# CoreProcessor.net
KiCad netlist of a schematic drawn in Altium Designer
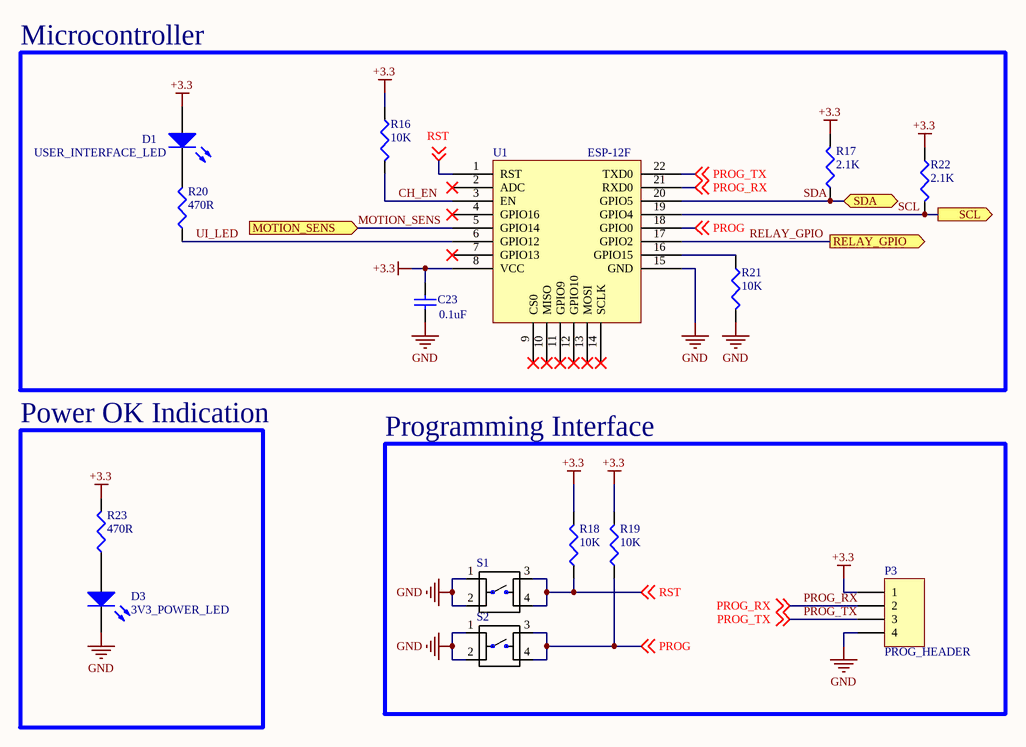
[diagram p0: CoreProcessor.SchDoc]

(export (version "E")
  (design (tool "Eeschema 10.0.6"))
  (components
    (comp (ref "C23")
      (value "0.1uF")
      (footprint "C0603")
      (description "Capacitor (Semiconductor SIM Model)")
      (fields (field (name "Comment") "MUDAR FOOTPRINT") (field (name "PUBLISHER") "Altium Limited"))
      (libsource (lib "Miscellaneous Devices") (part "Cap Semi"))
    )
    (comp (ref "D1")
      (value "USER_INTERFACE_LED")
      (footprint "LED0603")
      (description "Typical INFRARED GaAs LED")
      (fields (field (name "PUBLISHER") "Altium Limited"))
      (libsource (lib "Miscellaneous Devices") (part "LED0"))
    )
    (comp (ref "D3")
      (value "3V3_POWER_LED")
      (footprint "LED0603")
      (description "Typical INFRARED GaAs LED")
      (fields (field (name "PUBLISHER") "Altium Limited"))
      (libsource (lib "Miscellaneous Devices") (part "LED0"))
    )
    (comp (ref "P3")
      (value "PROG_HEADER")
      (footprint "HDR1X4")
      (description "Header, 4-Pin")
      (fields (field (name "PUBLISHER") "Altium Limited"))
      (libsource (lib "Miscellaneous Connectors") (part "Header 4"))
    )
    (comp (ref "R16")
      (value "10K")
      (footprint "R0603")
      (description "Resistor")
      (fields (field (name "Comment") "Res3") (field (name "PUBLISHER") "Altium Limited"))
      (libsource (lib "Miscellaneous Devices") (part "Res3"))
    )
    (comp (ref "R17")
      (value "2.1K")
      (footprint "R0603")
      (description "Resistor")
      (fields (field (name "Comment") "Res3") (field (name "PUBLISHER") "Altium Limited"))
      (libsource (lib "Miscellaneous Devices") (part "Res3"))
    )
    (comp (ref "R18")
      (value "10K")
      (footprint "R0603")
      (description "Resistor")
      (fields (field (name "Comment") "Res3") (field (name "PUBLISHER") "Altium Limited"))
      (libsource (lib "Miscellaneous Devices") (part "Res3"))
    )
    (comp (ref "R19")
      (value "10K")
      (footprint "R0603")
      (description "Resistor")
      (fields (field (name "Comment") "Res3") (field (name "PUBLISHER") "Altium Limited"))
      (libsource (lib "Miscellaneous Devices") (part "Res3"))
    )
    (comp (ref "R20")
      (value "470R")
      (footprint "R0603")
      (description "Resistor")
      (fields (field (name "Comment") "Res3") (field (name "PUBLISHER") "Altium Limited"))
      (libsource (lib "Miscellaneous Devices") (part "Res3"))
    )
    (comp (ref "R21")
      (value "10K")
      (footprint "R0603")
      (description "Resistor")
      (fields (field (name "Comment") "Res3") (field (name "PUBLISHER") "Altium Limited"))
      (libsource (lib "Miscellaneous Devices") (part "Res3"))
    )
    (comp (ref "R22")
      (value "2.1K")
      (footprint "R0603")
      (description "Resistor")
      (fields (field (name "Comment") "Res3") (field (name "PUBLISHER") "Altium Limited"))
      (libsource (lib "Miscellaneous Devices") (part "Res3"))
    )
    (comp (ref "R23")
      (value "470R")
      (footprint "R0603")
      (description "Resistor")
      (fields (field (name "Comment") "Res3") (field (name "PUBLISHER") "Altium Limited"))
      (libsource (lib "Miscellaneous Devices") (part "Res3"))
    )
    (comp (ref "S1")
      (value "FSM8JH")
      (footprint "SW_FSM8JH")
      (description "Switch, Pushbutton, Tactile, SPST, Thru Hole, Vertical, 6MM, Black")
      (fields (field (name "MF") "TE Connectivity / Alcoswitch"))
      (libsource (lib "PowerMonitoring") (part "BUTTON"))
    )
    (comp (ref "S2")
      (value "FSM8JH")
      (footprint "SW_FSM8JH")
      (description "Switch, Pushbutton, Tactile, SPST, Thru Hole, Vertical, 6MM, Black")
      (fields (field (name "MF") "TE Connectivity / Alcoswitch"))
      (libsource (lib "PowerMonitoring") (part "BUTTON"))
    )
    (comp (ref "U1")
      (value "ESP-12F")
      (footprint "XCVR_ESP8266-12E/ESP-12E")
      (libsource (lib "PowerMonitoring") (part "ESP-12F"))
    )
  )
  (nets
    (net (code "1") (name "+3.3") (class "Default")
      (node (ref "C23") (pin "2") (pinfunction "2_2") (pintype "passive"))
      (node (ref "D1") (pin "2") (pinfunction "A_2") (pintype "passive"))
      (node (ref "P3") (pin "1") (pinfunction "1_1") (pintype "passive"))
      (node (ref "R16") (pin "1") (pinfunction "1_1") (pintype "passive"))
      (node (ref "R17") (pin "2") (pinfunction "2_2") (pintype "passive"))
      (node (ref "R18") (pin "2") (pinfunction "2_2") (pintype "passive"))
      (node (ref "R19") (pin "2") (pinfunction "2_2") (pintype "passive"))
      (node (ref "R22") (pin "2") (pinfunction "2_2") (pintype "passive"))
      (node (ref "R23") (pin "2") (pinfunction "2_2") (pintype "passive"))
      (node (ref "U1") (pin "8") (pinfunction "VCC_8") (pintype "passive"))
    )
    (net (code "2") (name "/CH_EN") (class "Default")
      (node (ref "R16") (pin "2") (pinfunction "2_2") (pintype "passive"))
      (node (ref "U1") (pin "3") (pinfunction "EN_3") (pintype "passive"))
    )
    (net (code "3") (name "/MOTION_SENS") (class "Default")
      (node (ref "U1") (pin "5") (pinfunction "GPIO14_5") (pintype "passive"))
    )
    (net (code "4") (name "/RELAY_GPIO") (class "Default")
      (node (ref "U1") (pin "17") (pinfunction "GPIO2_17") (pintype "passive"))
    )
    (net (code "5") (name "/SCL") (class "Default")
      (node (ref "R22") (pin "1") (pinfunction "1_1") (pintype "passive"))
      (node (ref "U1") (pin "19") (pinfunction "GPIO4_19") (pintype "passive"))
    )
    (net (code "6") (name "/SDA") (class "Default")
      (node (ref "R17") (pin "1") (pinfunction "1_1") (pintype "passive"))
      (node (ref "U1") (pin "20") (pinfunction "GPIO5_20") (pintype "passive"))
    )
    (net (code "7") (name "/UI_LED") (class "Default")
      (node (ref "R20") (pin "1") (pinfunction "1_1") (pintype "passive"))
      (node (ref "U1") (pin "6") (pinfunction "GPIO12_6") (pintype "passive"))
    )
    (net (code "8") (name "GND") (class "Default")
      (node (ref "C23") (pin "1") (pinfunction "1_1") (pintype "passive"))
      (node (ref "D3") (pin "1") (pinfunction "K_1") (pintype "passive"))
      (node (ref "P3") (pin "4") (pinfunction "4_4") (pintype "passive"))
      (node (ref "R21") (pin "2") (pinfunction "2_2") (pintype "passive"))
      (node (ref "S1") (pin "1") (pinfunction "1_1") (pintype "passive"))
      (node (ref "S1") (pin "2") (pinfunction "2_2") (pintype "passive"))
      (node (ref "S2") (pin "1") (pinfunction "1_1") (pintype "passive"))
      (node (ref "S2") (pin "2") (pinfunction "2_2") (pintype "passive"))
      (node (ref "U1") (pin "15") (pinfunction "GND_15") (pintype "passive"))
    )
    (net (code "9") (name "Net-(D1-K)") (class "Default")
      (node (ref "D1") (pin "1") (pinfunction "K_1") (pintype "passive"))
      (node (ref "R20") (pin "2") (pinfunction "2_2") (pintype "passive"))
    )
    (net (code "10") (name "Net-(D3-A)") (class "Default")
      (node (ref "D3") (pin "2") (pinfunction "A_2") (pintype "passive"))
      (node (ref "R23") (pin "1") (pinfunction "1_1") (pintype "passive"))
    )
    (net (code "11") (name "Net-(U1-GPIO15)") (class "Default")
      (node (ref "R21") (pin "1") (pinfunction "1_1") (pintype "passive"))
      (node (ref "U1") (pin "16") (pinfunction "GPIO15_16") (pintype "passive"))
    )
    (net (code "12") (name "PROG") (class "Default")
      (node (ref "R19") (pin "1") (pinfunction "1_1") (pintype "passive"))
      (node (ref "S2") (pin "3") (pinfunction "3_3") (pintype "passive"))
      (node (ref "S2") (pin "4") (pinfunction "4_4") (pintype "passive"))
      (node (ref "U1") (pin "18") (pinfunction "GPIO0_18") (pintype "passive"))
    )
    (net (code "13") (name "PROG_RX") (class "Default")
      (node (ref "P3") (pin "2") (pinfunction "2_2") (pintype "passive"))
      (node (ref "U1") (pin "21") (pinfunction "RXD0_21") (pintype "passive"))
    )
    (net (code "14") (name "PROG_TX") (class "Default")
      (node (ref "P3") (pin "3") (pinfunction "3_3") (pintype "passive"))
      (node (ref "U1") (pin "22") (pinfunction "TXD0_22") (pintype "passive"))
    )
    (net (code "15") (name "RST") (class "Default")
      (node (ref "R18") (pin "1") (pinfunction "1_1") (pintype "passive"))
      (node (ref "S1") (pin "3") (pinfunction "3_3") (pintype "passive"))
      (node (ref "S1") (pin "4") (pinfunction "4_4") (pintype "passive"))
      (node (ref "U1") (pin "1") (pinfunction "RST_1") (pintype "passive"))
    )
    (net (code "16") (name "unconnected-(U1-ADC-Pad2)") (class "Default")
      (node (ref "U1") (pin "2") (pinfunction "ADC_2") (pintype "passive+no_connect"))
    )
    (net (code "17") (name "unconnected-(U1-CS0-Pad9)") (class "Default")
      (node (ref "U1") (pin "9") (pinfunction "CS0_9") (pintype "passive+no_connect"))
    )
    (net (code "18") (name "unconnected-(U1-GPIO9-Pad11)") (class "Default")
      (node (ref "U1") (pin "11") (pinfunction "GPIO9_11") (pintype "passive+no_connect"))
    )
    (net (code "19") (name "unconnected-(U1-GPIO10-Pad12)") (class "Default")
      (node (ref "U1") (pin "12") (pinfunction "GPIO10_12") (pintype "passive+no_connect"))
    )
    (net (code "20") (name "unconnected-(U1-GPIO13-Pad7)") (class "Default")
      (node (ref "U1") (pin "7") (pinfunction "GPIO13_7") (pintype "passive+no_connect"))
    )
    (net (code "21") (name "unconnected-(U1-GPIO16-Pad4)") (class "Default")
      (node (ref "U1") (pin "4") (pinfunction "GPIO16_4") (pintype "passive+no_connect"))
    )
    (net (code "22") (name "unconnected-(U1-MISO-Pad10)") (class "Default")
      (node (ref "U1") (pin "10") (pinfunction "MISO_10") (pintype "passive+no_connect"))
    )
    (net (code "23") (name "unconnected-(U1-MOSI-Pad13)") (class "Default")
      (node (ref "U1") (pin "13") (pinfunction "MOSI_13") (pintype "passive+no_connect"))
    )
    (net (code "24") (name "unconnected-(U1-SCLK-Pad14)") (class "Default")
      (node (ref "U1") (pin "14") (pinfunction "SCLK_14") (pintype "passive+no_connect"))
    )
  )
)
